# SCH_IOT2025_2025-10-15.net
KiCad netlist of a schematic drawn in EasyEDA
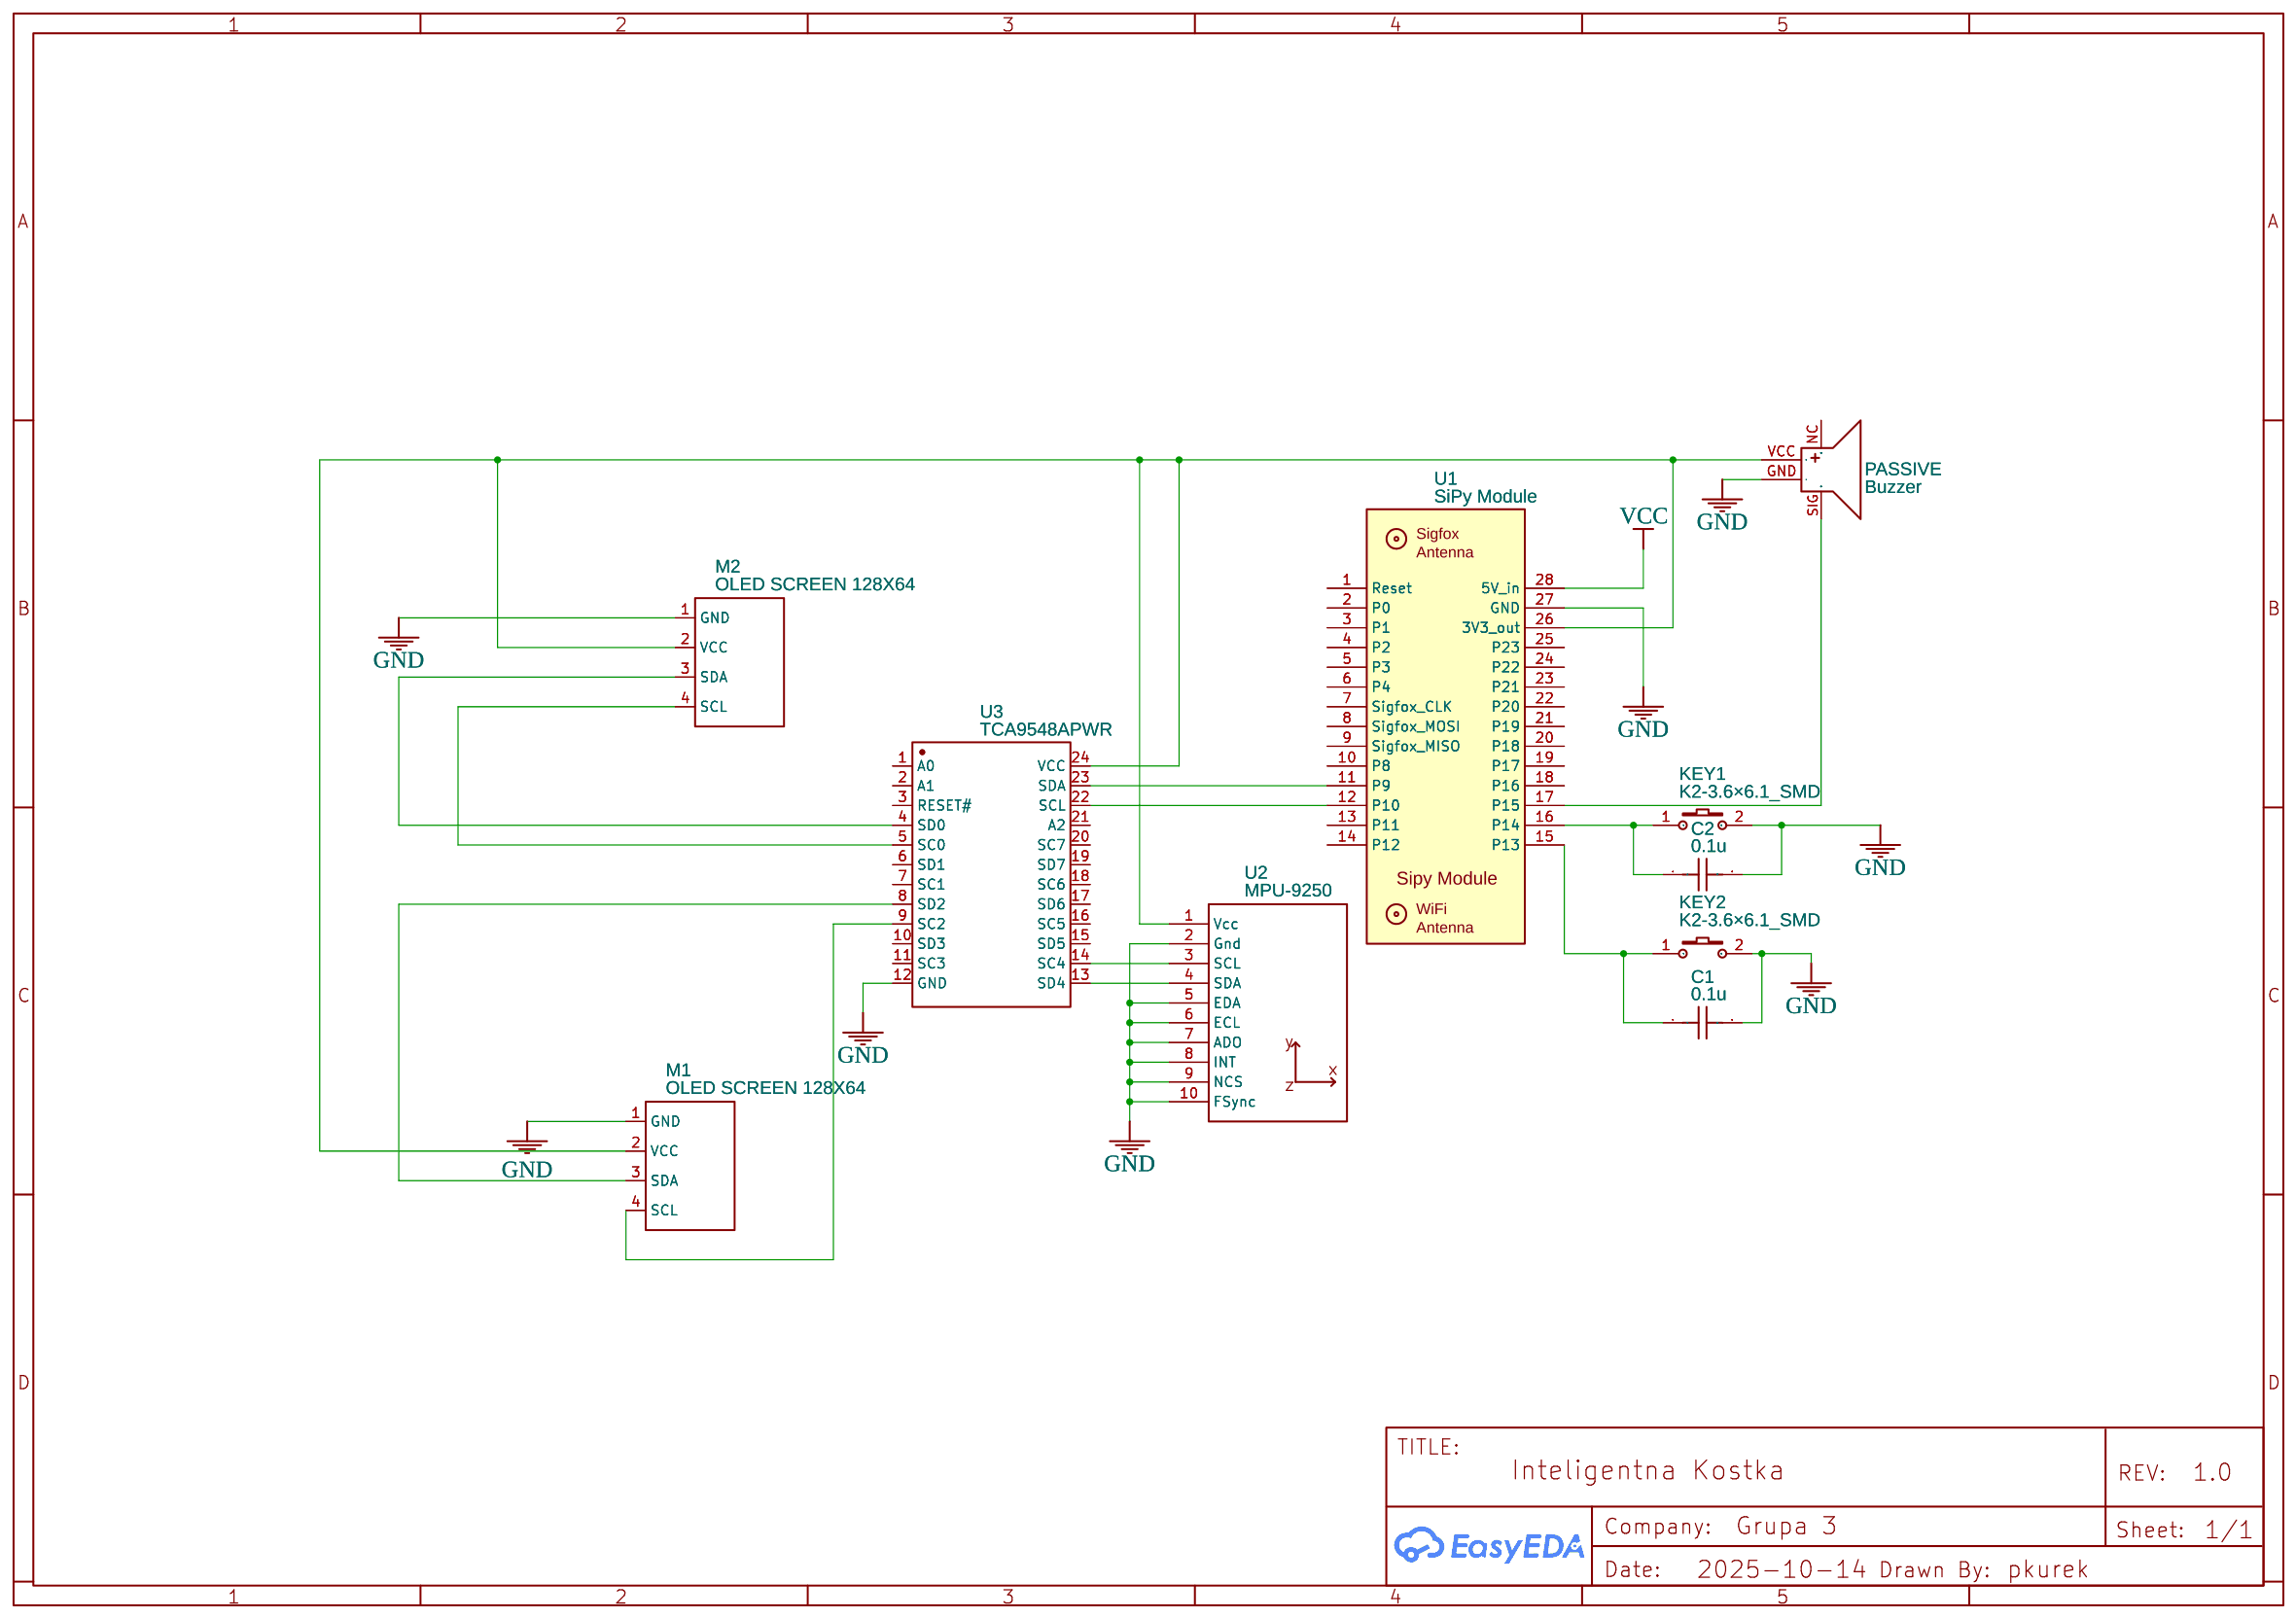
[diagram p0: schematic sheet]

(export (version "E")
  (design (tool "Eeschema 10.0.6"))
  (components
    (comp (ref "C1") (value "0.1u") (libsource (lib "") (part "C_0603_US")))
    (comp (ref "C2") (value "0.1u") (libsource (lib "") (part "C_0603_US")))
    (comp (ref "KEY1")
      (value "K2-3.6×6.1_SMD")
      (fields (field (name "Manufacturer Part") "K2-1107ST-A4SW-06"))
      (libsource (lib "") (part "K2-3.6×6.1_SMD"))
    )
    (comp (ref "KEY2")
      (value "K2-3.6×6.1_SMD")
      (fields (field (name "Manufacturer Part") "K2-1107ST-A4SW-06"))
      (libsource (lib "") (part "K2-3.6×6.1_SMD"))
    )
    (comp (ref "M1") (value "OLED SCREEN 128X64") (libsource (lib "") (part "LCD 16X2 I2C")))
    (comp (ref "M2") (value "OLED SCREEN 128X64") (libsource (lib "") (part "LCD 16X2 I2C")))
    (comp (ref "PASSIVE")
      (value "Buzzer")
      (fields (field (name "Manufacturer Part") "MLT-8530"))
      (libsource (lib "") (part "MLT-8530_C9900000449"))
    )
    (comp (ref "U1")
      (value "SiPy Module")
      (fields (field (name "Manufacturer Part") "https://pycom.io/product/sipy/"))
      (libsource (lib "") (part "SiPy Module"))
    )
    (comp (ref "U2") (value "MPU-9250") (libsource (lib "") (part "MPU-9250")))
    (comp (ref "U3")
      (value "TCA9548APWR")
      (fields (field (name "Manufacturer") "TI(德州仪器)"))
      (libsource (lib "") (part "TCA9548APWR"))
    )
  )
  (nets
    (net (code "1") (name "GND") (class "Default")
      (node (ref "C1") (pin "2") (pinfunction "2_2") (pintype "unspecified"))
      (node (ref "C2") (pin "2") (pinfunction "2_2") (pintype "unspecified"))
      (node (ref "KEY1") (pin "2") (pinfunction "2_2") (pintype "unspecified"))
      (node (ref "KEY2") (pin "2") (pinfunction "2_2") (pintype "unspecified"))
      (node (ref "M1") (pin "1") (pinfunction "GND_1") (pintype "unspecified"))
      (node (ref "M2") (pin "1") (pinfunction "GND_1") (pintype "unspecified"))
      (node (ref "PASSIVE") (pin "GND") (pinfunction "-_GND") (pintype "unspecified"))
      (node (ref "U1") (pin "27") (pinfunction "GND_27") (pintype "passive"))
      (node (ref "U2") (pin "10") (pinfunction "FSync_10") (pintype "unspecified"))
      (node (ref "U2") (pin "2") (pinfunction "Gnd_2") (pintype "passive"))
      (node (ref "U2") (pin "5") (pinfunction "EDA_5") (pintype "unspecified"))
      (node (ref "U2") (pin "6") (pinfunction "ECL_6") (pintype "unspecified"))
      (node (ref "U2") (pin "7") (pinfunction "ADO_7") (pintype "unspecified"))
      (node (ref "U2") (pin "8") (pinfunction "INT_8") (pintype "unspecified"))
      (node (ref "U2") (pin "9") (pinfunction "NCS_9") (pintype "unspecified"))
      (node (ref "U3") (pin "12") (pinfunction "GND_12") (pintype "unspecified"))
    )
    (net (code "2") (name "Net-(M1-SCL)") (class "Default")
      (node (ref "M1") (pin "4") (pinfunction "SCL_4") (pintype "unspecified"))
      (node (ref "U3") (pin "9") (pinfunction "SC2_9") (pintype "unspecified"))
    )
    (net (code "3") (name "Net-(M1-SDA)") (class "Default")
      (node (ref "M1") (pin "3") (pinfunction "SDA_3") (pintype "unspecified"))
      (node (ref "U3") (pin "8") (pinfunction "SD2_8") (pintype "unspecified"))
    )
    (net (code "4") (name "Net-(M1-VCC)") (class "Default")
      (node (ref "M1") (pin "2") (pinfunction "VCC_2") (pintype "unspecified"))
      (node (ref "M2") (pin "2") (pinfunction "VCC_2") (pintype "unspecified"))
      (node (ref "PASSIVE") (pin "VCC") (pinfunction "+_VCC") (pintype "unspecified"))
      (node (ref "U1") (pin "26") (pinfunction "3V3_out_26") (pintype "unspecified"))
      (node (ref "U2") (pin "1") (pinfunction "Vcc_1") (pintype "passive"))
      (node (ref "U3") (pin "24") (pinfunction "VCC_24") (pintype "unspecified"))
    )
    (net (code "5") (name "Net-(M2-SCL)") (class "Default")
      (node (ref "M2") (pin "4") (pinfunction "SCL_4") (pintype "unspecified"))
      (node (ref "U3") (pin "5") (pinfunction "SC0_5") (pintype "unspecified"))
    )
    (net (code "6") (name "Net-(M2-SDA)") (class "Default")
      (node (ref "M2") (pin "3") (pinfunction "SDA_3") (pintype "unspecified"))
      (node (ref "U3") (pin "4") (pinfunction "SD0_4") (pintype "unspecified"))
    )
    (net (code "7") (name "Net-(U1-P9)") (class "Default")
      (node (ref "U1") (pin "11") (pinfunction "P9_11") (pintype "unspecified"))
      (node (ref "U3") (pin "23") (pinfunction "SDA_23") (pintype "unspecified"))
    )
    (net (code "8") (name "Net-(U1-P10)") (class "Default")
      (node (ref "U1") (pin "12") (pinfunction "P10_12") (pintype "unspecified"))
      (node (ref "U3") (pin "22") (pinfunction "SCL_22") (pintype "unspecified"))
    )
    (net (code "9") (name "Net-(U1-P13)") (class "Default")
      (node (ref "C1") (pin "1") (pinfunction "1_1") (pintype "unspecified"))
      (node (ref "KEY2") (pin "1") (pinfunction "1_1") (pintype "unspecified"))
      (node (ref "U1") (pin "15") (pinfunction "P13_15") (pintype "unspecified"))
    )
    (net (code "10") (name "Net-(U1-P14)") (class "Default")
      (node (ref "C2") (pin "1") (pinfunction "1_1") (pintype "unspecified"))
      (node (ref "KEY1") (pin "1") (pinfunction "1_1") (pintype "unspecified"))
      (node (ref "U1") (pin "16") (pinfunction "P14_16") (pintype "unspecified"))
    )
    (net (code "11") (name "Net-(U1-P15)") (class "Default")
      (node (ref "PASSIVE") (pin "SIG") (pinfunction "NC_SIG") (pintype "unspecified"))
      (node (ref "U1") (pin "17") (pinfunction "P15_17") (pintype "unspecified"))
    )
    (net (code "12") (name "Net-(U2-SCL)") (class "Default")
      (node (ref "U2") (pin "3") (pinfunction "SCL_3") (pintype "unspecified"))
      (node (ref "U3") (pin "14") (pinfunction "SC4_14") (pintype "unspecified"))
    )
    (net (code "13") (name "Net-(U2-SDA)") (class "Default")
      (node (ref "U2") (pin "4") (pinfunction "SDA_4") (pintype "unspecified"))
      (node (ref "U3") (pin "13") (pinfunction "SD4_13") (pintype "unspecified"))
    )
    (net (code "14") (name "VCC") (class "Default")
      (node (ref "U1") (pin "28") (pinfunction "5V_in_28") (pintype "passive"))
    )
    (net (code "15") (name "unconnected-(PASSIVE-PadNC)") (class "Default")
      (node (ref "PASSIVE") (pin "NC") (pinfunction "NC_NC") (pintype "unspecified"))
    )
    (net (code "16") (name "unconnected-(U1-P0-Pad2)") (class "Default")
      (node (ref "U1") (pin "2") (pinfunction "P0_2") (pintype "unspecified"))
    )
    (net (code "17") (name "unconnected-(U1-P1-Pad3)") (class "Default")
      (node (ref "U1") (pin "3") (pinfunction "P1_3") (pintype "unspecified"))
    )
    (net (code "18") (name "unconnected-(U1-P2-Pad4)") (class "Default")
      (node (ref "U1") (pin "4") (pinfunction "P2_4") (pintype "unspecified"))
    )
    (net (code "19") (name "unconnected-(U1-P3-Pad5)") (class "Default")
      (node (ref "U1") (pin "5") (pinfunction "P3_5") (pintype "unspecified"))
    )
    (net (code "20") (name "unconnected-(U1-P4-Pad6)") (class "Default")
      (node (ref "U1") (pin "6") (pinfunction "P4_6") (pintype "unspecified"))
    )
    (net (code "21") (name "unconnected-(U1-P8-Pad10)") (class "Default")
      (node (ref "U1") (pin "10") (pinfunction "P8_10") (pintype "unspecified"))
    )
    (net (code "22") (name "unconnected-(U1-P11-Pad13)") (class "Default")
      (node (ref "U1") (pin "13") (pinfunction "P11_13") (pintype "unspecified"))
    )
    (net (code "23") (name "unconnected-(U1-P12-Pad14)") (class "Default")
      (node (ref "U1") (pin "14") (pinfunction "P12_14") (pintype "unspecified"))
    )
    (net (code "24") (name "unconnected-(U1-P16-Pad18)") (class "Default")
      (node (ref "U1") (pin "18") (pinfunction "P16_18") (pintype "unspecified"))
    )
    (net (code "25") (name "unconnected-(U1-P17-Pad19)") (class "Default")
      (node (ref "U1") (pin "19") (pinfunction "P17_19") (pintype "unspecified"))
    )
    (net (code "26") (name "unconnected-(U1-P18-Pad20)") (class "Default")
      (node (ref "U1") (pin "20") (pinfunction "P18_20") (pintype "unspecified"))
    )
    (net (code "27") (name "unconnected-(U1-P19-Pad21)") (class "Default")
      (node (ref "U1") (pin "21") (pinfunction "P19_21") (pintype "unspecified"))
    )
    (net (code "28") (name "unconnected-(U1-P20-Pad22)") (class "Default")
      (node (ref "U1") (pin "22") (pinfunction "P20_22") (pintype "unspecified"))
    )
    (net (code "29") (name "unconnected-(U1-P21-Pad23)") (class "Default")
      (node (ref "U1") (pin "23") (pinfunction "P21_23") (pintype "unspecified"))
    )
    (net (code "30") (name "unconnected-(U1-P22-Pad24)") (class "Default")
      (node (ref "U1") (pin "24") (pinfunction "P22_24") (pintype "unspecified"))
    )
    (net (code "31") (name "unconnected-(U1-P23-Pad25)") (class "Default")
      (node (ref "U1") (pin "25") (pinfunction "P23_25") (pintype "unspecified"))
    )
    (net (code "32") (name "unconnected-(U1-Reset-Pad1)") (class "Default")
      (node (ref "U1") (pin "1") (pinfunction "Reset_1") (pintype "unspecified"))
    )
    (net (code "33") (name "unconnected-(U1-Sigfox_CLK-Pad7)") (class "Default")
      (node (ref "U1") (pin "7") (pinfunction "Sigfox_CLK_7") (pintype "unspecified"))
    )
    (net (code "34") (name "unconnected-(U1-Sigfox_MISO-Pad9)") (class "Default")
      (node (ref "U1") (pin "9") (pinfunction "Sigfox_MISO_9") (pintype "unspecified"))
    )
    (net (code "35") (name "unconnected-(U1-Sigfox_MOSI-Pad8)") (class "Default")
      (node (ref "U1") (pin "8") (pinfunction "Sigfox_MOSI_8") (pintype "unspecified"))
    )
    (net (code "36") (name "unconnected-(U3-A0-Pad1)") (class "Default")
      (node (ref "U3") (pin "1") (pinfunction "A0_1") (pintype "unspecified"))
    )
    (net (code "37") (name "unconnected-(U3-A1-Pad2)") (class "Default")
      (node (ref "U3") (pin "2") (pinfunction "A1_2") (pintype "unspecified"))
    )
    (net (code "38") (name "unconnected-(U3-A2-Pad21)") (class "Default")
      (node (ref "U3") (pin "21") (pinfunction "A2_21") (pintype "unspecified"))
    )
    (net (code "39") (name "unconnected-(U3-RESET#-Pad3)") (class "Default")
      (node (ref "U3") (pin "3") (pinfunction "RESET#_3") (pintype "unspecified"))
    )
    (net (code "40") (name "unconnected-(U3-SC1-Pad7)") (class "Default")
      (node (ref "U3") (pin "7") (pinfunction "SC1_7") (pintype "unspecified"))
    )
    (net (code "41") (name "unconnected-(U3-SC3-Pad11)") (class "Default")
      (node (ref "U3") (pin "11") (pinfunction "SC3_11") (pintype "unspecified"))
    )
    (net (code "42") (name "unconnected-(U3-SC5-Pad16)") (class "Default")
      (node (ref "U3") (pin "16") (pinfunction "SC5_16") (pintype "unspecified"))
    )
    (net (code "43") (name "unconnected-(U3-SC6-Pad18)") (class "Default")
      (node (ref "U3") (pin "18") (pinfunction "SC6_18") (pintype "unspecified"))
    )
    (net (code "44") (name "unconnected-(U3-SC7-Pad20)") (class "Default")
      (node (ref "U3") (pin "20") (pinfunction "SC7_20") (pintype "unspecified"))
    )
    (net (code "45") (name "unconnected-(U3-SD1-Pad6)") (class "Default")
      (node (ref "U3") (pin "6") (pinfunction "SD1_6") (pintype "unspecified"))
    )
    (net (code "46") (name "unconnected-(U3-SD3-Pad10)") (class "Default")
      (node (ref "U3") (pin "10") (pinfunction "SD3_10") (pintype "unspecified"))
    )
    (net (code "47") (name "unconnected-(U3-SD5-Pad15)") (class "Default")
      (node (ref "U3") (pin "15") (pinfunction "SD5_15") (pintype "unspecified"))
    )
    (net (code "48") (name "unconnected-(U3-SD6-Pad17)") (class "Default")
      (node (ref "U3") (pin "17") (pinfunction "SD6_17") (pintype "unspecified"))
    )
    (net (code "49") (name "unconnected-(U3-SD7-Pad19)") (class "Default")
      (node (ref "U3") (pin "19") (pinfunction "SD7_19") (pintype "unspecified"))
    )
  )
)
